# PCB_TX.net
KiCad netlist of a schematic drawn in Altium Designer
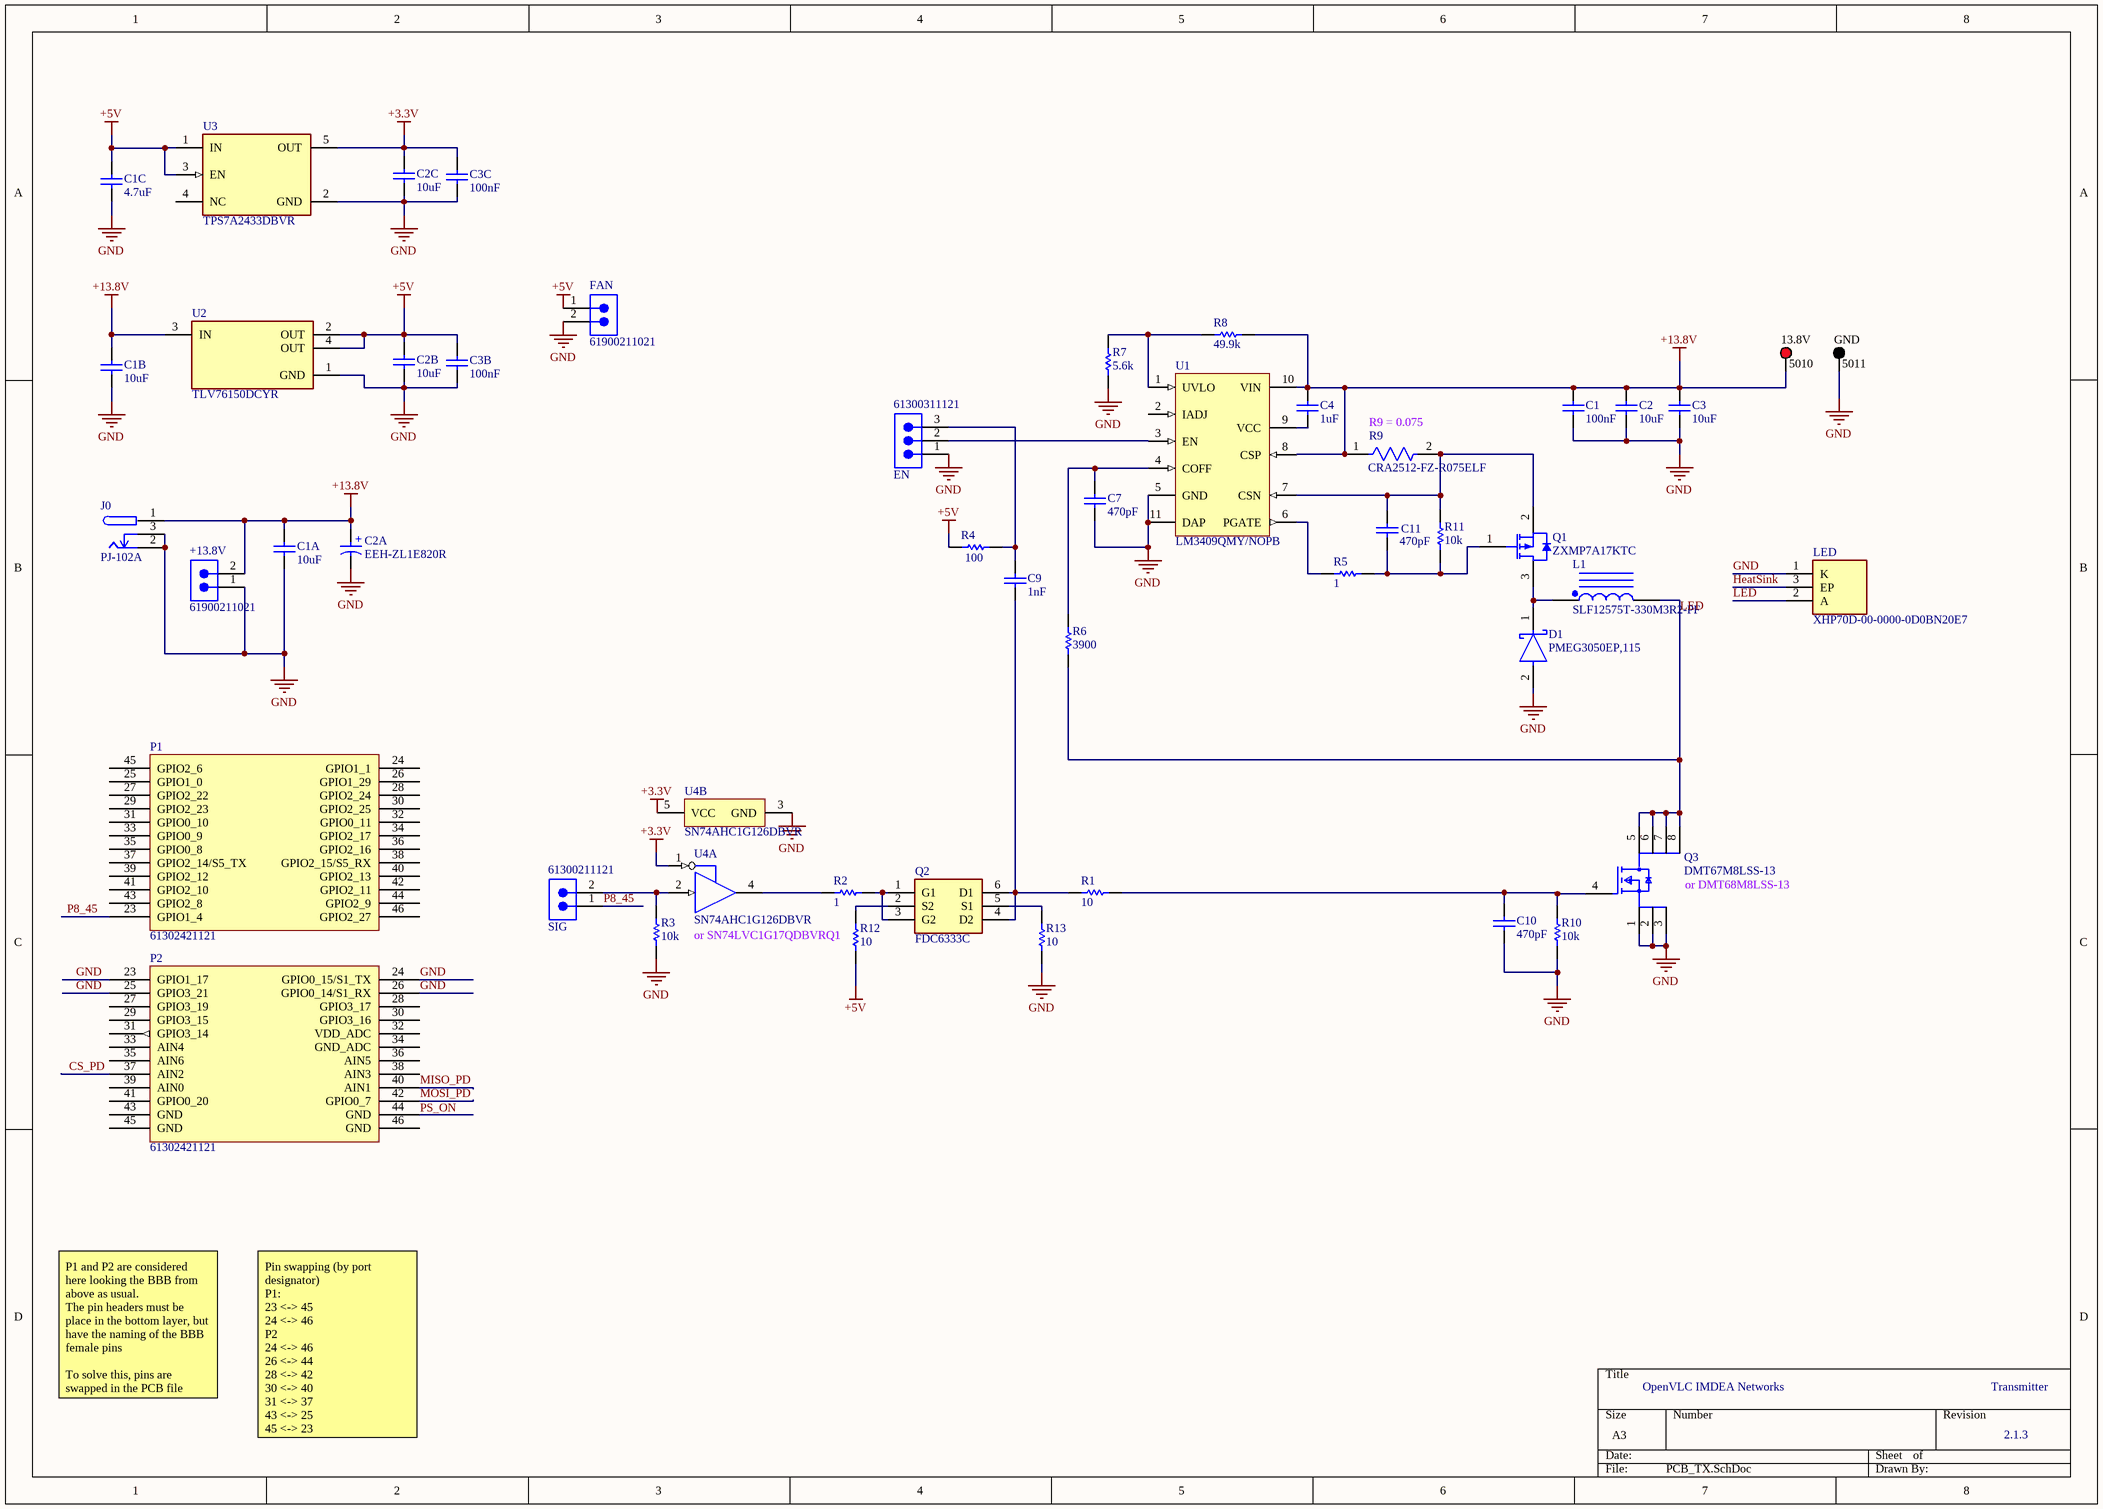
[diagram p0: PCB_TX.SchDoc]

(export (version "E")
  (design (tool "Eeschema 10.0.6"))
  (components
    (comp (ref "+13.8V")
      (value "61900211021")
      (footprint "61900211021")
      (libsource (lib "Altium Content Vault") (part "Header_Male_1R_02P"))
    )
    (comp (ref "13.8V")
      (value "5010")
      (footprint "KSTN-5010_V")
      (description "Test Point, Red, Through Hole, RoHS, Bulk")
      (fields (field (name "MANUFACTURER") "Keystone"))
      (libsource (lib "Altium Content Vault") (part "TESTPOINT_RED"))
    )
    (comp (ref "C1")
      (value "100nF")
      (footprint "RESC1608X55N")
      (description "Capacitor")
      (fields (field (name "Comment") "GCM188R71H104KA57J") (field (name "PUBLISHER") "Altium Limited"))
      (libsource (lib "Miscellaneous Devices") (part "Cap"))
    )
    (comp (ref "C1A")
      (value "10uF")
      (footprint "RESC1608X55N")
      (description "Capacitor")
      (fields (field (name "Comment") "GRM188R6YA106MA73D") (field (name "PUBLISHER") "Altium Limited"))
      (libsource (lib "Miscellaneous Devices") (part "Cap"))
    )
    (comp (ref "C1B")
      (value "10uF")
      (footprint "RESC1608X55N")
      (description "Capacitor")
      (fields (field (name "Comment") "GRM188R6YA475KE15D") (field (name "PUBLISHER") "Altium Limited"))
      (libsource (lib "Miscellaneous Devices") (part "Cap"))
    )
    (comp (ref "C1C")
      (value "4.7uF")
      (footprint "RESC1608X55N")
      (description "Capacitor")
      (fields (field (name "Comment") "GRM188R6YA475KE15D") (field (name "PUBLISHER") "Altium Limited"))
      (libsource (lib "Miscellaneous Devices") (part "Cap"))
    )
    (comp (ref "C2")
      (value "10uF")
      (footprint "RESC1608X55N")
      (description "Capacitor")
      (fields (field (name "Comment") "GRM188R6YA106MA73D") (field (name "PUBLISHER") "Altium Limited"))
      (libsource (lib "Miscellaneous Devices") (part "Cap"))
    )
    (comp (ref "C2A")
      (value "EEH-ZL1E820R")
      (footprint "WCAP-PSLP_D5H5.5")
      (description "875105242006 WCAP-PSLP Aluminum Polymer Capacitors")
      (fields (field (name "TOLERANCE") "20%"))
      (libsource (lib "Altium Content Vault") (part "Capacitor_Polarized"))
    )
    (comp (ref "C2B")
      (value "10uF")
      (footprint "RESC1608X55N")
      (description "Capacitor")
      (fields (field (name "Comment") "GRM188R6YA106MA73D") (field (name "PUBLISHER") "Altium Limited"))
      (libsource (lib "Miscellaneous Devices") (part "Cap"))
    )
    (comp (ref "C2C")
      (value "10uF")
      (footprint "RESC1608X55N")
      (description "Capacitor")
      (fields (field (name "Comment") "GRM188R6YA106MA73D") (field (name "PUBLISHER") "Altium Limited"))
      (libsource (lib "Miscellaneous Devices") (part "Cap"))
    )
    (comp (ref "C3")
      (value "10uF")
      (footprint "RESC1608X55N")
      (description "Capacitor")
      (fields (field (name "Comment") "GRM188R6YA106MA73D") (field (name "PUBLISHER") "Altium Limited"))
      (libsource (lib "Miscellaneous Devices") (part "Cap"))
    )
    (comp (ref "C3B")
      (value "100nF")
      (footprint "RESC1608X55N")
      (description "Capacitor")
      (fields (field (name "Comment") "GCM188R71H104KA57J") (field (name "PUBLISHER") "Altium Limited"))
      (libsource (lib "Miscellaneous Devices") (part "Cap"))
    )
    (comp (ref "C3C")
      (value "100nF")
      (footprint "RESC1608X55N")
      (description "Capacitor")
      (fields (field (name "Comment") "GCM188R71H104KA57J") (field (name "PUBLISHER") "Altium Limited"))
      (libsource (lib "Miscellaneous Devices") (part "Cap"))
    )
    (comp (ref "C4")
      (value "1uF")
      (footprint "RESC1608X55N")
      (description "Capacitor")
      (fields (field (name "Comment") "GCM188D71H105KE36J") (field (name "PUBLISHER") "Altium Limited"))
      (libsource (lib "Miscellaneous Devices") (part "Cap"))
    )
    (comp (ref "C7")
      (value "470pF")
      (footprint "RESC1608X55N")
      (description "Capacitor")
      (fields (field (name "Comment") "GCM1885C1H471JA16D") (field (name "PUBLISHER") "Altium Limited"))
      (libsource (lib "Miscellaneous Devices") (part "Cap"))
    )
    (comp (ref "C9")
      (value "1nF")
      (footprint "RESC1608X55N")
      (description "Capacitor")
      (fields (field (name "Comment") "GRM1885C1H102JA01D") (field (name "PUBLISHER") "Altium Limited"))
      (libsource (lib "Miscellaneous Devices") (part "Cap"))
    )
    (comp (ref "C10")
      (value "470pF")
      (footprint "RESC1608X55N")
      (description "Capacitor")
      (fields (field (name "Comment") "GCM1885C1H471JA16D") (field (name "PUBLISHER") "Altium Limited"))
      (libsource (lib "Miscellaneous Devices") (part "Cap"))
    )
    (comp (ref "C11")
      (value "470pF")
      (footprint "RESC1608X55N")
      (description "Capacitor")
      (fields (field (name "Comment") "GCM1885C1H471JA16D") (field (name "PUBLISHER") "Altium Limited"))
      (libsource (lib "Miscellaneous Devices") (part "Cap"))
    )
    (comp (ref "D1")
      (value "PMEG3050EP,115")
      (footprint "FP-SOD128-MFG")
      (description "DIODE SCHOTTKY 30V 5A SOD128")
      (libsource (lib "Altium Content Vault") (part "1d6ec82d83fb6aee721767c19dac4b9"))
    )
    (comp (ref "EN")
      (value "61300311121")
      (footprint "61300311121")
      (libsource (lib "Altium Content Vault") (part "Header_Male_1R_03P"))
    )
    (comp (ref "FAN")
      (value "61900211021")
      (footprint "61900211021")
      (libsource (lib "Altium Content Vault") (part "Header_Male_1R_02P"))
    )
    (comp (ref "GND")
      (value "5011")
      (footprint "KSTN-5011_V")
      (description "Test Point, Black, Through Hole, RoHS, Bulk")
      (fields (field (name "MANUFACTURER") "Keystone"))
      (libsource (lib "Altium Content Vault") (part "TESTPOINT_BLACK"))
    )
    (comp (ref "J0")
      (value "PJ-102A")
      (footprint "FP-PJ-102A-MFG")
      (description "PJ-102A 2.0 x 6.5 mm, 2.5 A, Horizontal, Through Hole, Tapered Pins, Dc Power Jack Connector")
      (libsource (lib "Altium Content Vault") (part "c639f672d24b5d70918fa8d934b95d1"))
    )
    (comp (ref "L1")
      (value "SLF12575T-330M3R2-PF")
      (footprint "EATN-DR125_V")
      (fields (field (name "MANUFACTURER") "EATON"))
      (libsource (lib "Altium Content Vault") (part "IND-DOT-2"))
    )
    (comp (ref "LED")
      (value "XHP70D-00-0000-0D0BN20E7")
      (footprint "XHP70DH000000D0HN20E3_12")
      (description "High Power LEDs - White White 5000 K 80-CRI, XLamp XHP70D")
      (fields
        (field (name "MANUFACTURER_PART_NUMBER") "XHP70D-H0-0000-0D0HN20E3")
        (field (name "MOUSER PART NUMBER") "941-XHP70DH0D0HN20E3")
      )
      (libsource (lib "XHP70D-H0-0000-0D0HN20E3") (part "XHP70D-H0-0000-0D0HN20E3"))
    )
    (comp (ref "P1")
      (value "61302421121")
      (footprint "BBB_CAPE_NO_HEADER_R_24")
      (libsource (lib "BeagleBoneCape") (part "BBB_P8_reduced"))
    )
    (comp (ref "P2")
      (value "61302421121")
      (footprint "BBB_CAPE_NO_HEADER_R_24")
      (libsource (lib "BeagleBoneCape") (part "BBB_P9_reduced"))
    )
    (comp (ref "Q1")
      (value "ZXMP7A17KTC")
      (footprint "DIOD-TO252-3_V")
      (fields (field (name "MANUFACTURER") "Diodes Inc"))
      (libsource (lib "Altium Content Vault") (part "PEMOS-GSD-3"))
    )
    (comp (ref "Q2")
      (value "FDC6333C")
      (footprint "SOT95P275X110-6N")
      (fields (field (name "MOUSER PART NUMBER") "512-FDC6333C"))
      (libsource (lib "FDC6333C") (part "FDC6333C"))
    )
    (comp (ref "Q3")
      (value "DMT67M8LSS-13")
      (footprint "FP-751EB-MFG")
      (description "FDS2672-F085 Trans MOSFET N-CH 200V 3.9A Automotive 8-Pin SOIC T/R")
      (libsource (lib "Altium Content Vault") (part "a2191056e8335feadc5ee6660ea8eee"))
    )
    (comp (ref "R1")
      (value "10")
      (footprint "RESC1608X55N")
      (description "Resistor")
      (fields (field (name "Comment") "RT0603BRD0710RL") (field (name "PUBLISHER") "Altium Limited"))
      (libsource (lib "Miscellaneous Devices") (part "Res1"))
    )
    (comp (ref "R2")
      (value "1")
      (footprint "RESC1608X55N")
      (description "Resistor")
      (fields (field (name "Comment") "RT0603BRD071RL") (field (name "PUBLISHER") "Altium Limited"))
      (libsource (lib "Miscellaneous Devices") (part "Res1"))
    )
    (comp (ref "R3")
      (value "10k")
      (footprint "RESC1608X55N")
      (description "Resistor")
      (fields (field (name "Comment") "RT0603BRD0710KL") (field (name "PUBLISHER") "Altium Limited"))
      (libsource (lib "Miscellaneous Devices") (part "Res1"))
    )
    (comp (ref "R4")
      (value "100")
      (footprint "RESC1608X55N")
      (description "Resistor")
      (fields (field (name "Comment") "RT0603BRD07100RL") (field (name "PUBLISHER") "Altium Limited"))
      (libsource (lib "Miscellaneous Devices") (part "Res1"))
    )
    (comp (ref "R5")
      (value "1")
      (footprint "RESC1608X55N")
      (description "Resistor")
      (fields (field (name "Comment") "RT0603BRD0710RL") (field (name "PUBLISHER") "Altium Limited"))
      (libsource (lib "Miscellaneous Devices") (part "Res1"))
    )
    (comp (ref "R6")
      (value "3900")
      (footprint "RESC1608X55N")
      (description "Resistor")
      (fields (field (name "Comment") "RT0603BRD073K9L") (field (name "PUBLISHER") "Altium Limited"))
      (libsource (lib "Miscellaneous Devices") (part "Res1"))
    )
    (comp (ref "R7")
      (value "5.6k")
      (footprint "RESC1608X55N")
      (description "Resistor")
      (fields (field (name "Comment") "RT0603BRD075K76L") (field (name "PUBLISHER") "Altium Limited"))
      (libsource (lib "Miscellaneous Devices") (part "Res1"))
    )
    (comp (ref "R8")
      (value "49.9k")
      (footprint "RESC1608X55N")
      (description "Resistor")
      (fields (field (name "Comment") "RT0603BRD0749K9L") (field (name "PUBLISHER") "Altium Limited"))
      (libsource (lib "Miscellaneous Devices") (part "Res1"))
    )
    (comp (ref "R9")
      (value "CRA2512-FZ-R075ELF")
      (footprint "FP-CSRN2512-IPC_B")
      (description "Res Thick Film 2512 0.1Ω 1% 2W ±200ppm/°C Molded SMD Plastic T/R")
      (fields (field (name "TOLERANCE") "1%"))
      (libsource (lib "Altium Content Vault") (part "1029c3af85768c4190bb7ad29bc67b5"))
    )
    (comp (ref "R10")
      (value "10k")
      (footprint "RESC1608X55N")
      (description "Resistor")
      (fields (field (name "Comment") "RT0603BRD0710KL") (field (name "PUBLISHER") "Altium Limited"))
      (libsource (lib "Miscellaneous Devices") (part "Res1"))
    )
    (comp (ref "R11")
      (value "10k")
      (footprint "RESC1608X55N")
      (description "Resistor")
      (fields (field (name "Comment") "RT0603BRD0710KL") (field (name "PUBLISHER") "Altium Limited"))
      (libsource (lib "Miscellaneous Devices") (part "Res1"))
    )
    (comp (ref "R12")
      (value "10")
      (footprint "RESC1608X55N")
      (description "Resistor")
      (fields (field (name "Comment") "RT0603BRD0710RL") (field (name "PUBLISHER") "Altium Limited"))
      (libsource (lib "Miscellaneous Devices") (part "Res1"))
    )
    (comp (ref "R13")
      (value "10")
      (footprint "RESC1608X55N")
      (description "Resistor")
      (fields (field (name "Comment") "RT0603BRD0710RL") (field (name "PUBLISHER") "Altium Limited"))
      (libsource (lib "Miscellaneous Devices") (part "Res1"))
    )
    (comp (ref "SIG")
      (value "61300211121")
      (footprint "61300211121")
      (libsource (lib "Altium Content Vault") (part "Header_Male_1R_02P"))
    )
    (comp (ref "U1")
      (value "LM3409QMY/NOPB")
      (footprint "DGQ0010A_N")
      (description "PFET Buck Controller for High Power LED Drives, 10-pin eMSOP, Pb-Free")
      (fields (field (name "MANUFACTURER") "Texas Instruments"))
      (libsource (lib "Altium Content Vault") (part "IN-LEDD-LM3409-11"))
    )
    (comp (ref "U2")
      (value "TLV76150DCYR")
      (footprint "FP-DCY0004A-MFG")
      (description "TLV76150DCYR 1-A 16-V high-PSRR linear voltage regulator 4-SOT-223 -40 to 125")
      (libsource (lib "Altium Content Vault") (part "991ffb903c51cf6179ce9942c0606aa"))
    )
    (comp (ref "U3")
      (value "TPS7A2433DBVR")
      (footprint "FP-DBV0005A-MFG")
      (libsource (lib "Altium Content Vault") (part "ee7747973c1ed1d4cccbb20406fa51c"))
    )
    (comp (ref "U4")
      (value "SN74AHC1G126DBVR")
      (footprint "DBV0005A_M")
      (description "Single Bus Buffer Gate With 3-State Outputs, DBV0005A, LARGE T&R")
      (fields
        (field (name "GENERIC PART NUMBER") "SN74AHC1G126")
        (field (name "MANUFACTURER") "Texas Instruments")
      )
      (libsource (lib "Altium Content Vault") (part "TI-SN74XXXXXX126-5"))
    )
  )
  (nets
    (net (code "1") (name "+3.3V") (class "Default")
      (node (ref "C2C") (pin "2") (pinfunction "2_2") (pintype "passive"))
      (node (ref "C3C") (pin "1") (pinfunction "1_1") (pintype "passive"))
      (node (ref "U3") (pin "5") (pinfunction "OUT_5") (pintype "power_in"))
      (node (ref "U4") (pin "1") (pinfunction "OE_1") (pintype "input"))
      (node (ref "U4") (pin "5") (pinfunction "VCC_5") (pintype "power_in"))
    )
    (net (code "2") (name "+5V") (class "Default")
      (node (ref "C1C") (pin "2") (pinfunction "2_2") (pintype "passive"))
      (node (ref "C2B") (pin "2") (pinfunction "2_2") (pintype "passive"))
      (node (ref "C3B") (pin "1") (pinfunction "1_1") (pintype "passive"))
      (node (ref "FAN") (pin "1") (pinfunction "1_1") (pintype "passive"))
      (node (ref "R12") (pin "2") (pinfunction "2_2") (pintype "passive"))
      (node (ref "R4") (pin "2") (pinfunction "2_2") (pintype "passive"))
      (node (ref "U2") (pin "2") (pinfunction "OUT_2") (pintype "passive"))
      (node (ref "U2") (pin "4") (pinfunction "OUT_4") (pintype "passive"))
      (node (ref "U3") (pin "1") (pinfunction "IN_1") (pintype "power_in"))
      (node (ref "U3") (pin "3") (pinfunction "EN_3") (pintype "input"))
    )
    (net (code "3") (name "+13.8V") (class "Default")
      (node (ref "+13.8V") (pin "2") (pinfunction "2_2") (pintype "passive"))
      (node (ref "13.8V") (pin "1") (pinfunction "1_1") (pintype "passive"))
      (node (ref "C1") (pin "1") (pinfunction "1_1") (pintype "passive"))
      (node (ref "C1A") (pin "1") (pinfunction "1_1") (pintype "passive"))
      (node (ref "C1B") (pin "2") (pinfunction "2_2") (pintype "passive"))
      (node (ref "C2") (pin "1") (pinfunction "1_1") (pintype "passive"))
      (node (ref "C2A") (pin "1") (pinfunction "P_1") (pintype "passive"))
      (node (ref "C3") (pin "1") (pinfunction "1_1") (pintype "passive"))
      (node (ref "C4") (pin "1") (pinfunction "1_1") (pintype "passive"))
      (node (ref "J0") (pin "1") (pinfunction "1_1") (pintype "passive"))
      (node (ref "R8") (pin "1") (pinfunction "1_1") (pintype "passive"))
      (node (ref "R9") (pin "1") (pinfunction "1_1") (pintype "passive"))
      (node (ref "U1") (pin "10") (pinfunction "VIN_10") (pintype "power_in"))
      (node (ref "U1") (pin "8") (pinfunction "CSP_8") (pintype "input"))
      (node (ref "U2") (pin "3") (pinfunction "IN_3") (pintype "power_in"))
    )
    (net (code "4") (name "/CS_PD") (class "Default")
      (node (ref "P2") (pin "37") (pinfunction "AIN2_37") (pintype "passive"))
    )
    (net (code "5") (name "/HeatSink") (class "Default")
      (node (ref "LED") (pin "3") (pinfunction "EP_3") (pintype "passive"))
    )
    (net (code "6") (name "/LED") (class "Default")
      (node (ref "L1") (pin "2") (pinfunction "2_2") (pintype "passive"))
      (node (ref "LED") (pin "2") (pinfunction "A_2") (pintype "passive"))
      (node (ref "Q3") (pin "5") (pinfunction "D_5") (pintype "passive"))
      (node (ref "Q3") (pin "6") (pinfunction "D_6") (pintype "passive"))
      (node (ref "Q3") (pin "7") (pinfunction "D_7") (pintype "passive"))
      (node (ref "Q3") (pin "8") (pinfunction "D_8") (pintype "passive"))
      (node (ref "R6") (pin "2") (pinfunction "2_2") (pintype "passive"))
    )
    (net (code "7") (name "/MISO_PD") (class "Default")
      (node (ref "P2") (pin "40") (pinfunction "AIN1_40") (pintype "passive"))
    )
    (net (code "8") (name "/MOSI_PD") (class "Default")
      (node (ref "P2") (pin "42") (pinfunction "GPIO0_7_42") (pintype "passive"))
    )
    (net (code "9") (name "/P8_45") (class "Default")
      (node (ref "P1") (pin "23") (pinfunction "GPIO1_4_23") (pintype "passive"))
      (node (ref "SIG") (pin "1") (pinfunction "1_1") (pintype "passive"))
    )
    (net (code "11") (name "GND") (class "Default")
      (node (ref "+13.8V") (pin "1") (pinfunction "1_1") (pintype "passive"))
      (node (ref "C1") (pin "2") (pinfunction "2_2") (pintype "passive"))
      (node (ref "C10") (pin "2") (pinfunction "2_2") (pintype "passive"))
      (node (ref "C1A") (pin "2") (pinfunction "2_2") (pintype "passive"))
      (node (ref "C1B") (pin "1") (pinfunction "1_1") (pintype "passive"))
      (node (ref "C1C") (pin "1") (pinfunction "1_1") (pintype "passive"))
      (node (ref "C2") (pin "2") (pinfunction "2_2") (pintype "passive"))
      (node (ref "C2A") (pin "2") (pinfunction "N_2") (pintype "passive"))
      (node (ref "C2B") (pin "1") (pinfunction "1_1") (pintype "passive"))
      (node (ref "C2C") (pin "1") (pinfunction "1_1") (pintype "passive"))
      (node (ref "C3") (pin "2") (pinfunction "2_2") (pintype "passive"))
      (node (ref "C3B") (pin "2") (pinfunction "2_2") (pintype "passive"))
      (node (ref "C3C") (pin "2") (pinfunction "2_2") (pintype "passive"))
      (node (ref "C7") (pin "2") (pinfunction "2_2") (pintype "passive"))
      (node (ref "D1") (pin "2") (pinfunction "A_2") (pintype "passive"))
      (node (ref "EN") (pin "1") (pinfunction "1_1") (pintype "passive"))
      (node (ref "FAN") (pin "2") (pinfunction "2_2") (pintype "passive"))
      (node (ref "GND") (pin "1") (pinfunction "1_1") (pintype "passive"))
      (node (ref "J0") (pin "2") (pinfunction "2_2") (pintype "passive"))
      (node (ref "J0") (pin "3") (pinfunction "3_3") (pintype "passive"))
      (node (ref "LED") (pin "1") (pinfunction "K_1") (pintype "passive"))
      (node (ref "P2") (pin "23") (pinfunction "GPIO1_17_23") (pintype "passive"))
      (node (ref "P2") (pin "24") (pinfunction "GPIO0_15/S1_TX_24") (pintype "passive"))
      (node (ref "P2") (pin "25") (pinfunction "GPIO3_21_25") (pintype "passive"))
      (node (ref "P2") (pin "26") (pinfunction "GPIO0_14/S1_RX_26") (pintype "passive"))
      (node (ref "Q3") (pin "1") (pinfunction "S_1") (pintype "passive"))
      (node (ref "Q3") (pin "2") (pinfunction "S_2") (pintype "passive"))
      (node (ref "Q3") (pin "3") (pinfunction "S_3") (pintype "passive"))
      (node (ref "R10") (pin "2") (pinfunction "2_2") (pintype "passive"))
      (node (ref "R13") (pin "2") (pinfunction "2_2") (pintype "passive"))
      (node (ref "R3") (pin "2") (pinfunction "2_2") (pintype "passive"))
      (node (ref "R7") (pin "2") (pinfunction "2_2") (pintype "passive"))
      (node (ref "U1") (pin "11") (pinfunction "DAP_11") (pintype "power_in"))
      (node (ref "U1") (pin "5") (pinfunction "GND_5") (pintype "power_in"))
      (node (ref "U2") (pin "1") (pinfunction "GND_1") (pintype "power_in"))
      (node (ref "U3") (pin "2") (pinfunction "GND_2") (pintype "power_in"))
      (node (ref "U4") (pin "3") (pinfunction "GND_3") (pintype "power_in"))
    )
    (net (code "12") (name "Net-(C9-Pad1)") (class "Default")
      (node (ref "C9") (pin "1") (pinfunction "1_1") (pintype "passive"))
      (node (ref "EN") (pin "3") (pinfunction "3_3") (pintype "passive"))
      (node (ref "R4") (pin "1") (pinfunction "1_1") (pintype "passive"))
    )
    (net (code "13") (name "Net-(D1-C)") (class "Default")
      (node (ref "D1") (pin "1") (pinfunction "C_1") (pintype "passive"))
      (node (ref "L1") (pin "1") (pinfunction "1_1") (pintype "passive"))
      (node (ref "Q1") (pin "3") (pinfunction "DRAIN_3") (pintype "passive"))
    )
    (net (code "14") (name "Net-(Q1-GATE)") (class "Default")
      (node (ref "C11") (pin "2") (pinfunction "2_2") (pintype "passive"))
      (node (ref "Q1") (pin "1") (pinfunction "GATE_1") (pintype "passive"))
      (node (ref "R11") (pin "2") (pinfunction "2_2") (pintype "passive"))
      (node (ref "R5") (pin "1") (pinfunction "1_1") (pintype "passive"))
    )
    (net (code "15") (name "Net-(Q1-SOURCE)") (class "Default")
      (node (ref "C11") (pin "1") (pinfunction "1_1") (pintype "passive"))
      (node (ref "Q1") (pin "2") (pinfunction "SOURCE_2") (pintype "passive"))
      (node (ref "R11") (pin "1") (pinfunction "1_1") (pintype "passive"))
      (node (ref "R9") (pin "2") (pinfunction "2_2") (pintype "passive"))
      (node (ref "U1") (pin "7") (pinfunction "CSN_7") (pintype "input"))
    )
    (net (code "16") (name "Net-(Q2-D1)") (class "Default")
      (node (ref "C9") (pin "2") (pinfunction "2_2") (pintype "passive"))
      (node (ref "Q2") (pin "4") (pinfunction "D2_4") (pintype "passive"))
      (node (ref "Q2") (pin "6") (pinfunction "D1_6") (pintype "passive"))
      (node (ref "R1") (pin "2") (pinfunction "2_2") (pintype "passive"))
    )
    (net (code "17") (name "Net-(Q2-G1)") (class "Default")
      (node (ref "Q2") (pin "1") (pinfunction "G1_1") (pintype "passive"))
      (node (ref "Q2") (pin "3") (pinfunction "G2_3") (pintype "passive"))
      (node (ref "R2") (pin "1") (pinfunction "1_1") (pintype "passive"))
    )
    (net (code "18") (name "Net-(Q2-S1)") (class "Default")
      (node (ref "Q2") (pin "5") (pinfunction "S1_5") (pintype "passive"))
      (node (ref "R13") (pin "1") (pinfunction "1_1") (pintype "passive"))
    )
    (net (code "19") (name "Net-(Q2-S2)") (class "Default")
      (node (ref "Q2") (pin "2") (pinfunction "S2_2") (pintype "passive"))
      (node (ref "R12") (pin "1") (pinfunction "1_1") (pintype "passive"))
    )
    (net (code "20") (name "Net-(Q3-G)") (class "Default")
      (node (ref "C10") (pin "1") (pinfunction "1_1") (pintype "passive"))
      (node (ref "Q3") (pin "4") (pinfunction "G_4") (pintype "passive"))
      (node (ref "R1") (pin "1") (pinfunction "1_1") (pintype "passive"))
      (node (ref "R10") (pin "1") (pinfunction "1_1") (pintype "passive"))
    )
    (net (code "21") (name "Net-(U1-COFF)") (class "Default")
      (node (ref "C7") (pin "1") (pinfunction "1_1") (pintype "passive"))
      (node (ref "R6") (pin "1") (pinfunction "1_1") (pintype "passive"))
      (node (ref "U1") (pin "4") (pinfunction "COFF_4") (pintype "input"))
    )
    (net (code "22") (name "Net-(U1-EN)") (class "Default")
      (node (ref "EN") (pin "2") (pinfunction "2_2") (pintype "passive"))
      (node (ref "U1") (pin "3") (pinfunction "EN_3") (pintype "input"))
    )
    (net (code "23") (name "Net-(U1-PGATE)") (class "Default")
      (node (ref "R5") (pin "2") (pinfunction "2_2") (pintype "passive"))
      (node (ref "U1") (pin "6") (pinfunction "PGATE_6") (pintype "output"))
    )
    (net (code "24") (name "Net-(U1-UVLO)") (class "Default")
      (node (ref "R7") (pin "1") (pinfunction "1_1") (pintype "passive"))
      (node (ref "R8") (pin "2") (pinfunction "2_2") (pintype "passive"))
      (node (ref "U1") (pin "1") (pinfunction "UVLO_1") (pintype "input"))
    )
    (net (code "25") (name "Net-(U1-VCC)") (class "Default")
      (node (ref "C4") (pin "2") (pinfunction "2_2") (pintype "passive"))
      (node (ref "U1") (pin "9") (pinfunction "VCC_9") (pintype "power_in"))
    )
    (net (code "26") (name "Net-(U4A-A)") (class "Default")
      (node (ref "R3") (pin "1") (pinfunction "1_1") (pintype "passive"))
      (node (ref "SIG") (pin "2") (pinfunction "2_2") (pintype "passive"))
      (node (ref "U4") (pin "2") (pinfunction "A_2") (pintype "input"))
    )
    (net (code "27") (name "Net-(U4A-Y)") (class "Default")
      (node (ref "R2") (pin "2") (pinfunction "2_2") (pintype "passive"))
      (node (ref "U4") (pin "4") (pinfunction "Y_4") (pintype "tri_state"))
    )
    (net (code "28") (name "unconnected-(P1-GPIO0_8-Pad35)") (class "Default")
      (node (ref "P1") (pin "35") (pinfunction "GPIO0_8_35") (pintype "passive"))
    )
    (net (code "29") (name "unconnected-(P1-GPIO0_9-Pad33)") (class "Default")
      (node (ref "P1") (pin "33") (pinfunction "GPIO0_9_33") (pintype "passive"))
    )
    (net (code "30") (name "unconnected-(P1-GPIO0_10-Pad31)") (class "Default")
      (node (ref "P1") (pin "31") (pinfunction "GPIO0_10_31") (pintype "passive"))
    )
    (net (code "31") (name "unconnected-(P1-GPIO0_11-Pad32)") (class "Default")
      (node (ref "P1") (pin "32") (pinfunction "GPIO0_11_32") (pintype "passive"))
    )
    (net (code "32") (name "unconnected-(P1-GPIO1_0-Pad25)") (class "Default")
      (node (ref "P1") (pin "25") (pinfunction "GPIO1_0_25") (pintype "passive"))
    )
    (net (code "33") (name "unconnected-(P1-GPIO1_1-Pad24)") (class "Default")
      (node (ref "P1") (pin "24") (pinfunction "GPIO1_1_24") (pintype "passive"))
    )
    (net (code "34") (name "unconnected-(P1-GPIO1_29-Pad26)") (class "Default")
      (node (ref "P1") (pin "26") (pinfunction "GPIO1_29_26") (pintype "passive"))
    )
    (net (code "35") (name "unconnected-(P1-GPIO2_6-Pad45)") (class "Default")
      (node (ref "P1") (pin "45") (pinfunction "GPIO2_6_45") (pintype "passive"))
    )
    (net (code "36") (name "unconnected-(P1-GPIO2_8-Pad43)") (class "Default")
      (node (ref "P1") (pin "43") (pinfunction "GPIO2_8_43") (pintype "passive"))
    )
    (net (code "37") (name "unconnected-(P1-GPIO2_9-Pad44)") (class "Default")
      (node (ref "P1") (pin "44") (pinfunction "GPIO2_9_44") (pintype "passive"))
    )
    (net (code "38") (name "unconnected-(P1-GPIO2_10-Pad41)") (class "Default")
      (node (ref "P1") (pin "41") (pinfunction "GPIO2_10_41") (pintype "passive"))
    )
    (net (code "39") (name "unconnected-(P1-GPIO2_11-Pad42)") (class "Default")
      (node (ref "P1") (pin "42") (pinfunction "GPIO2_11_42") (pintype "passive"))
    )
    (net (code "40") (name "unconnected-(P1-GPIO2_12-Pad39)") (class "Default")
      (node (ref "P1") (pin "39") (pinfunction "GPIO2_12_39") (pintype "passive"))
    )
    (net (code "41") (name "unconnected-(P1-GPIO2_13-Pad40)") (class "Default")
      (node (ref "P1") (pin "40") (pinfunction "GPIO2_13_40") (pintype "passive"))
    )
    (net (code "42") (name "unconnected-(P1-GPIO2_14{slash}S5_TX-Pad37)") (class "Default")
      (node (ref "P1") (pin "37") (pinfunction "GPIO2_14/S5_TX_37") (pintype "passive"))
    )
    (net (code "43") (name "unconnected-(P1-GPIO2_15{slash}S5_RX-Pad38)") (class "Default")
      (node (ref "P1") (pin "38") (pinfunction "GPIO2_15/S5_RX_38") (pintype "passive"))
    )
    (net (code "44") (name "unconnected-(P1-GPIO2_16-Pad36)") (class "Default")
      (node (ref "P1") (pin "36") (pinfunction "GPIO2_16_36") (pintype "passive"))
    )
    (net (code "45") (name "unconnected-(P1-GPIO2_17-Pad34)") (class "Default")
      (node (ref "P1") (pin "34") (pinfunction "GPIO2_17_34") (pintype "passive"))
    )
    (net (code "46") (name "unconnected-(P1-GPIO2_22-Pad27)") (class "Default")
      (node (ref "P1") (pin "27") (pinfunction "GPIO2_22_27") (pintype "passive"))
    )
    (net (code "47") (name "unconnected-(P1-GPIO2_23-Pad29)") (class "Default")
      (node (ref "P1") (pin "29") (pinfunction "GPIO2_23_29") (pintype "passive"))
    )
    (net (code "48") (name "unconnected-(P1-GPIO2_24-Pad28)") (class "Default")
      (node (ref "P1") (pin "28") (pinfunction "GPIO2_24_28") (pintype "passive"))
    )
    (net (code "49") (name "unconnected-(P1-GPIO2_25-Pad30)") (class "Default")
      (node (ref "P1") (pin "30") (pinfunction "GPIO2_25_30") (pintype "passive"))
    )
    (net (code "50") (name "unconnected-(P1-GPIO2_27-Pad46)") (class "Default")
      (node (ref "P1") (pin "46") (pinfunction "GPIO2_27_46") (pintype "passive"))
    )
    (net (code "51") (name "unconnected-(P2-AIN0-Pad39)") (class "Default")
      (node (ref "P2") (pin "39") (pinfunction "AIN0_39") (pintype "passive"))
    )
    (net (code "52") (name "unconnected-(P2-AIN3-Pad38)") (class "Default")
      (node (ref "P2") (pin "38") (pinfunction "AIN3_38") (pintype "passive"))
    )
    (net (code "53") (name "unconnected-(P2-AIN4-Pad33)") (class "Default")
      (node (ref "P2") (pin "33") (pinfunction "AIN4_33") (pintype "passive"))
    )
    (net (code "54") (name "unconnected-(P2-AIN5-Pad36)") (class "Default")
      (node (ref "P2") (pin "36") (pinfunction "AIN5_36") (pintype "passive"))
    )
    (net (code "55") (name "unconnected-(P2-AIN6-Pad35)") (class "Default")
      (node (ref "P2") (pin "35") (pinfunction "AIN6_35") (pintype "passive"))
    )
    (net (code "56") (name "unconnected-(P2-GND-Pad43)") (class "Default")
      (node (ref "P2") (pin "43") (pinfunction "GND_43") (pintype "passive"))
    )
    (net (code "57") (name "unconnected-(P2-GND-Pad44)") (class "Default")
      (node (ref "P2") (pin "44") (pinfunction "GND_44") (pintype "passive"))
    )
    (net (code "58") (name "unconnected-(P2-GND-Pad45)") (class "Default")
      (node (ref "P2") (pin "45") (pinfunction "GND_45") (pintype "passive"))
    )
    (net (code "59") (name "unconnected-(P2-GND-Pad46)") (class "Default")
      (node (ref "P2") (pin "46") (pinfunction "GND_46") (pintype "passive"))
    )
    (net (code "60") (name "unconnected-(P2-GND_ADC-Pad34)") (class "Default")
      (node (ref "P2") (pin "34") (pinfunction "GND_ADC_34") (pintype "passive"))
    )
    (net (code "61") (name "unconnected-(P2-GPIO0_20-Pad41)") (class "Default")
      (node (ref "P2") (pin "41") (pinfunction "GPIO0_20_41") (pintype "passive"))
    )
    (net (code "62") (name "unconnected-(P2-GPIO3_14-Pad31)") (class "Default")
      (node (ref "P2") (pin "31") (pinfunction "GPIO3_14_31") (pintype "output"))
    )
    (net (code "63") (name "unconnected-(P2-GPIO3_15-Pad29)") (class "Default")
      (node (ref "P2") (pin "29") (pinfunction "GPIO3_15_29") (pintype "passive"))
    )
    (net (code "64") (name "unconnected-(P2-GPIO3_16-Pad30)") (class "Default")
      (node (ref "P2") (pin "30") (pinfunction "GPIO3_16_30") (pintype "passive"))
    )
    (net (code "65") (name "unconnected-(P2-GPIO3_17-Pad28)") (class "Default")
      (node (ref "P2") (pin "28") (pinfunction "GPIO3_17_28") (pintype "passive"))
    )
    (net (code "66") (name "unconnected-(P2-GPIO3_19-Pad27)") (class "Default")
      (node (ref "P2") (pin "27") (pinfunction "GPIO3_19_27") (pintype "passive"))
    )
    (net (code "67") (name "unconnected-(P2-VDD_ADC-Pad32)") (class "Default")
      (node (ref "P2") (pin "32") (pinfunction "VDD_ADC_32") (pintype "passive"))
    )
    (net (code "68") (name "unconnected-(U1-IADJ-Pad2)") (class "Default")
      (node (ref "U1") (pin "2") (pinfunction "IADJ_2") (pintype "input"))
    )
    (net (code "69") (name "unconnected-(U3-NC-Pad4)") (class "Default")
      (node (ref "U3") (pin "4") (pinfunction "NC_4") (pintype "passive"))
    )
  )
)
